# waterlezer.net
KiCad netlist of a schematic drawn in EAGLE
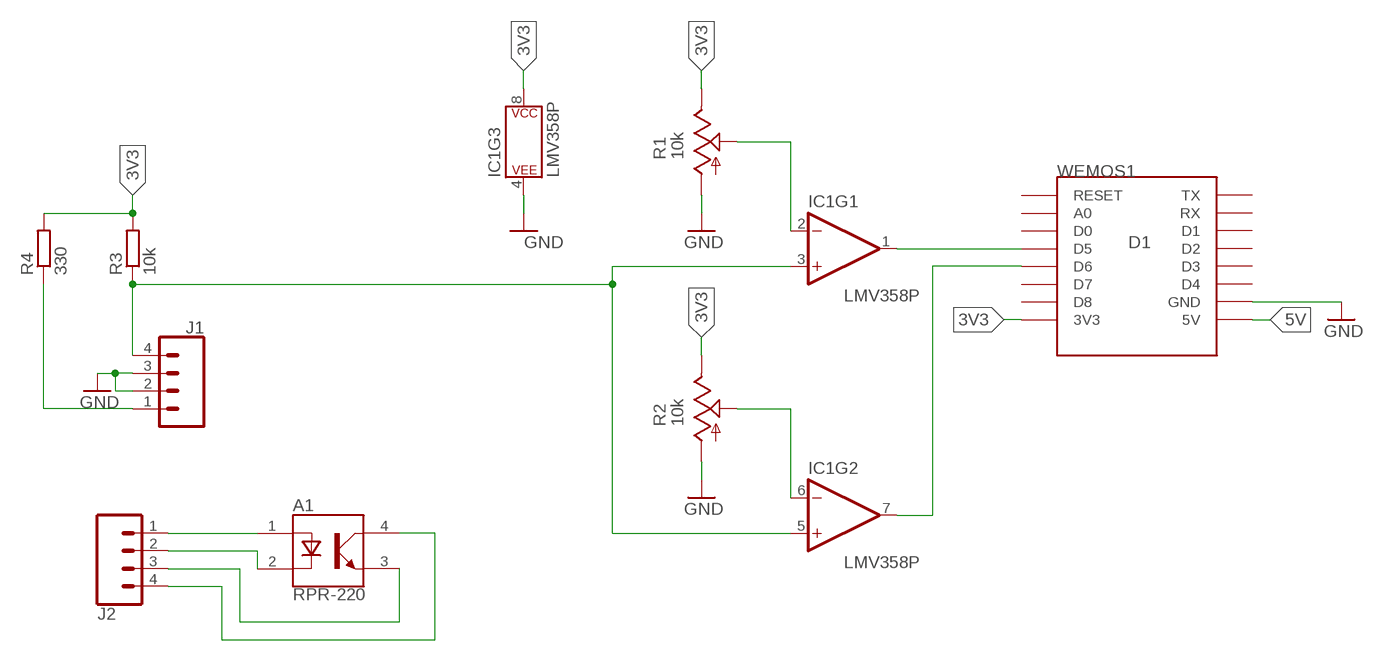
[diagram p0: schematic, sheet 1]

(export (version "E")
  (design (tool "Eeschema 10.0.6"))
  (components
    (comp (ref "A1")
      (value "RPR-220")
      (footprint "eagle-import:PHODET_RPR-220")
      (fields (field (name "MF") "Rohm"))
      (libsource (lib "eagle-import") (part "RPR-220"))
    )
    (comp (ref "IC1")
      (value "LMV358P")
      (footprint "eagle-import:DIP08")
      (libsource (lib "eagle-import") (part "OPAMP-DUALDIP"))
    )
    (comp (ref "J1")
      (value "CONN_04POLAR")
      (footprint "eagle-import:MOLEX-1X4")
      (libsource (lib "eagle-import") (part "CONN_04POLAR"))
    )
    (comp (ref "J2")
      (value "CONN_04POLAR")
      (footprint "eagle-import:MOLEX-1X4")
      (libsource (lib "eagle-import") (part "CONN_04POLAR"))
    )
    (comp (ref "R1")
      (value "10k")
      (footprint "eagle-import:S63P")
      (libsource (lib "eagle-import") (part "TRIM_US-S63P"))
    )
    (comp (ref "R2")
      (value "10k")
      (footprint "eagle-import:S63P")
      (libsource (lib "eagle-import") (part "TRIM_US-S63P"))
    )
    (comp (ref "R3")
      (value "10k")
      (footprint "eagle-import:0207_10")
      (libsource (lib "eagle-import") (part "R-EU_0207/10"))
    )
    (comp (ref "R4")
      (value "330")
      (footprint "eagle-import:0207_10")
      (libsource (lib "eagle-import") (part "R-EU_0207/10"))
    )
    (comp (ref "WEMOS1")
      (value "D1")
      (footprint "eagle-import:WEMOS-D1-MINI")
      (libsource (lib "eagle-import") (part "WEMOS-D1-MINI"))
    )
  )
  (nets
    (net (code "1") (name "3V3") (class "Default")
      (node (ref "IC1") (pin "8") (pinfunction "P$V+_8") (pintype "bidirectional"))
      (node (ref "R1") (pin "E") (pinfunction "E_E") (pintype "passive"))
      (node (ref "R2") (pin "E") (pinfunction "E_E") (pintype "passive"))
      (node (ref "R3") (pin "2") (pinfunction "2_2") (pintype "passive"))
      (node (ref "R4") (pin "2") (pinfunction "2_2") (pintype "passive"))
      (node (ref "WEMOS1") (pin "3V3") (pinfunction "3V3_3V3") (pintype "bidirectional"))
    )
    (net (code "2") (name "5V") (class "Default")
      (node (ref "WEMOS1") (pin "5V") (pinfunction "5V_5V") (pintype "bidirectional"))
    )
    (net (code "3") (name "GND") (class "Default")
      (node (ref "IC1") (pin "4") (pinfunction "P$V-_4") (pintype "bidirectional"))
      (node (ref "J1") (pin "2") (pinfunction "2_2") (pintype "passive"))
      (node (ref "J1") (pin "3") (pinfunction "3_3") (pintype "passive"))
      (node (ref "R1") (pin "A") (pinfunction "A_A") (pintype "passive"))
      (node (ref "R2") (pin "A") (pinfunction "A_A") (pintype "passive"))
      (node (ref "WEMOS1") (pin "GND") (pinfunction "GND_GND") (pintype "bidirectional"))
    )
    (net (code "4") (name "Net-(A1-ANODE)") (class "Default")
      (node (ref "A1") (pin "1") (pinfunction "ANODE_1") (pintype "passive"))
      (node (ref "J2") (pin "1") (pinfunction "1_1") (pintype "passive"))
    )
    (net (code "5") (name "Net-(A1-CATHODE)") (class "Default")
      (node (ref "A1") (pin "2") (pinfunction "CATHODE_2") (pintype "passive"))
      (node (ref "J2") (pin "2") (pinfunction "2_2") (pintype "passive"))
    )
    (net (code "6") (name "Net-(A1-COLLECTOR)") (class "Default")
      (node (ref "A1") (pin "4") (pinfunction "COLLECTOR_4") (pintype "passive"))
      (node (ref "J2") (pin "4") (pinfunction "4_4") (pintype "passive"))
    )
    (net (code "7") (name "Net-(A1-EMITTER)") (class "Default")
      (node (ref "A1") (pin "3") (pinfunction "EMITTER_3") (pintype "passive"))
      (node (ref "J2") (pin "3") (pinfunction "3_3") (pintype "passive"))
    )
    (net (code "8") (name "Net-(IC1A-+IN)") (class "Default")
      (node (ref "IC1") (pin "3") (pinfunction "+IN_3") (pintype "input"))
      (node (ref "IC1") (pin "5") (pinfunction "+IN_5") (pintype "input"))
      (node (ref "J1") (pin "4") (pinfunction "4_4") (pintype "passive"))
      (node (ref "R3") (pin "1") (pinfunction "1_1") (pintype "passive"))
    )
    (net (code "9") (name "Net-(IC1A--IN)") (class "Default")
      (node (ref "IC1") (pin "2") (pinfunction "-IN_2") (pintype "input"))
      (node (ref "R1") (pin "S") (pinfunction "S_S") (pintype "passive"))
    )
    (net (code "10") (name "Net-(IC1A-OUT)") (class "Default")
      (node (ref "IC1") (pin "1") (pinfunction "OUT_1") (pintype "output"))
      (node (ref "WEMOS1") (pin "D5") (pinfunction "D5_D5") (pintype "bidirectional"))
    )
    (net (code "11") (name "Net-(IC1B--IN)") (class "Default")
      (node (ref "IC1") (pin "6") (pinfunction "-IN_6") (pintype "input"))
      (node (ref "R2") (pin "S") (pinfunction "S_S") (pintype "passive"))
    )
    (net (code "12") (name "Net-(IC1B-OUT)") (class "Default")
      (node (ref "IC1") (pin "7") (pinfunction "OUT_7") (pintype "output"))
      (node (ref "WEMOS1") (pin "D6") (pinfunction "D6_D6") (pintype "bidirectional"))
    )
    (net (code "13") (name "Net-(J1-Pad1)") (class "Default")
      (node (ref "J1") (pin "1") (pinfunction "1_1") (pintype "passive"))
      (node (ref "R4") (pin "1") (pinfunction "1_1") (pintype "passive"))
    )
    (net (code "14") (name "unconnected-(WEMOS1-PadA0)") (class "Default")
      (node (ref "WEMOS1") (pin "A0") (pinfunction "A0_A0") (pintype "bidirectional"))
    )
    (net (code "15") (name "unconnected-(WEMOS1-PadD0)") (class "Default")
      (node (ref "WEMOS1") (pin "D0") (pinfunction "D0_D0") (pintype "bidirectional"))
    )
    (net (code "16") (name "unconnected-(WEMOS1-PadD1)") (class "Default")
      (node (ref "WEMOS1") (pin "D1") (pinfunction "D1_D1") (pintype "bidirectional"))
    )
    (net (code "17") (name "unconnected-(WEMOS1-PadD2)") (class "Default")
      (node (ref "WEMOS1") (pin "D2") (pinfunction "D2_D2") (pintype "bidirectional"))
    )
    (net (code "18") (name "unconnected-(WEMOS1-PadD3)") (class "Default")
      (node (ref "WEMOS1") (pin "D3") (pinfunction "D3_D3") (pintype "bidirectional"))
    )
    (net (code "19") (name "unconnected-(WEMOS1-PadD4)") (class "Default")
      (node (ref "WEMOS1") (pin "D4") (pinfunction "D4_D4") (pintype "bidirectional"))
    )
    (net (code "20") (name "unconnected-(WEMOS1-PadD7)") (class "Default")
      (node (ref "WEMOS1") (pin "D7") (pinfunction "D7_D7") (pintype "bidirectional"))
    )
    (net (code "21") (name "unconnected-(WEMOS1-PadD8)") (class "Default")
      (node (ref "WEMOS1") (pin "D8") (pinfunction "D8_D8") (pintype "bidirectional"))
    )
    (net (code "22") (name "unconnected-(WEMOS1-PadRESET)") (class "Default")
      (node (ref "WEMOS1") (pin "RESET") (pinfunction "RESET_RESET") (pintype "bidirectional"))
    )
    (net (code "23") (name "unconnected-(WEMOS1-PadRX)") (class "Default")
      (node (ref "WEMOS1") (pin "RX") (pinfunction "RX_RX") (pintype "bidirectional"))
    )
    (net (code "24") (name "unconnected-(WEMOS1-PadTX)") (class "Default")
      (node (ref "WEMOS1") (pin "TX") (pinfunction "TX_TX") (pintype "bidirectional"))
    )
  )
)
